# design.net
KiCad netlist of a schematic drawn in Altium Designer
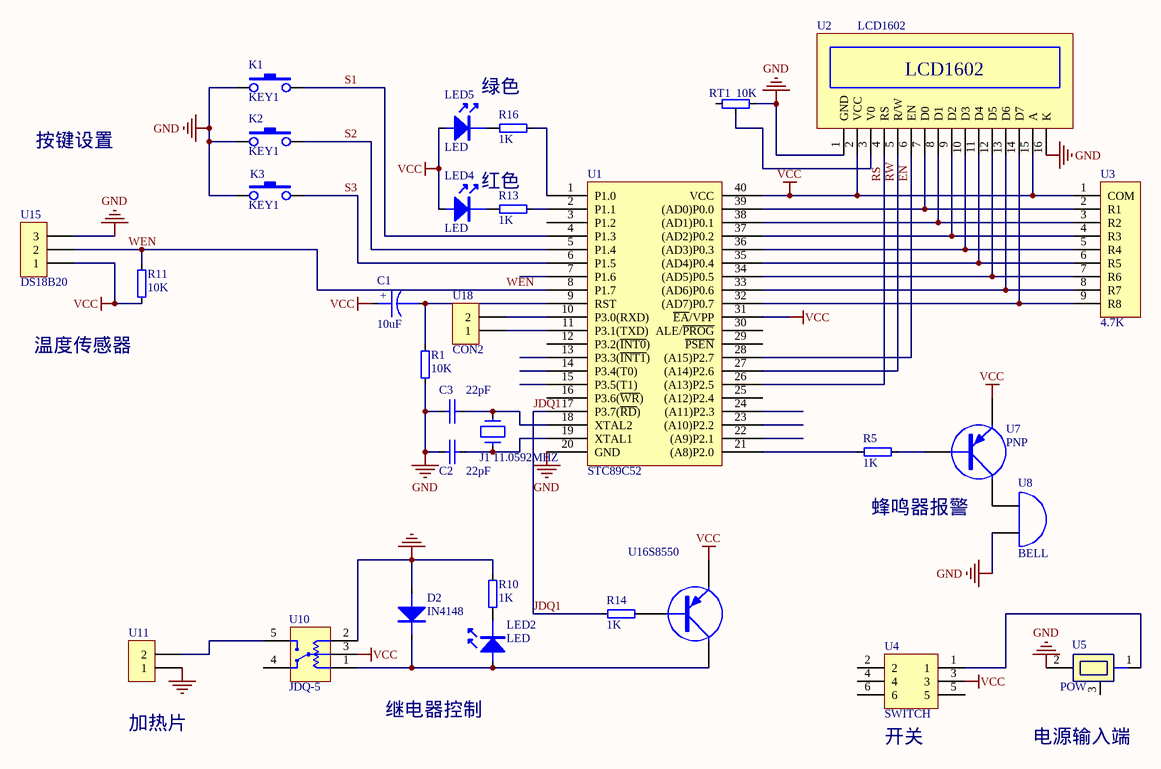
[diagram p0: 原理图.SchDoc]

(export (version "E")
  (design (tool "Eeschema 10.0.6"))
  (components
    (comp (ref "C1") (value "10uF") (footprint "C10") (libsource (lib "51SCH") (part "10uF")))
    (comp (ref "C2") (value "22pF") (footprint "CAP") (libsource (lib "51SCH") (part "0.1uF")))
    (comp (ref "C3") (value "22pF") (footprint "CAP") (libsource (lib "51SCH") (part "0.1uF")))
    (comp (ref "D2") (value "IN4148") (footprint "IN4148") (libsource (lib "*") (part "DIODE")))
    (comp (ref "J1") (value "11.0592MHZ") (footprint "CRYSTAL") (libsource (lib "51SCH") (part "CRYSTAL")))
    (comp (ref "K1") (value "KEY1") (footprint "KEY1") (libsource (lib "51SCH") (part "KEY1")))
    (comp (ref "K2") (value "KEY1") (footprint "KEY1") (libsource (lib "51SCH") (part "KEY1")))
    (comp (ref "K3") (value "KEY1") (footprint "KEY1") (libsource (lib "51SCH") (part "KEY1")))
    (comp (ref "LED2") (value "LED") (footprint "LED") (libsource (lib "*") (part "LED")))
    (comp (ref "LED4") (value "LED") (footprint "LED") (libsource (lib "*") (part "LED")))
    (comp (ref "LED5") (value "LED") (footprint "LED") (libsource (lib "*") (part "LED")))
    (comp (ref "R1") (value "10K") (footprint "R-DIP") (libsource (lib "51SCH") (part "10K")))
    (comp (ref "R5") (value "1K") (footprint "R-DIP") (libsource (lib "51SCH") (part "1K")))
    (comp (ref "R10") (value "1K") (footprint "R-DIP") (libsource (lib "*") (part "1K")))
    (comp (ref "R11") (value "10K") (footprint "R-DIP") (libsource (lib "51SCH") (part "10K")))
    (comp (ref "R13") (value "1K") (footprint "R-DIP") (libsource (lib "*") (part "1K")))
    (comp (ref "R14") (value "1K") (footprint "R-DIP") (libsource (lib "*") (part "1K")))
    (comp (ref "R16") (value "1K") (footprint "R-DIP") (libsource (lib "*") (part "1K")))
    (comp (ref "RT1") (value "10K") (footprint "RT1") (libsource (lib "51SCH") (part "RT")))
    (comp (ref "U1") (value "STC89C52") (footprint "STC") (libsource (lib "51SCH") (part "STC51")))
    (comp (ref "U2") (value "LCD1602") (footprint "LCD1602") (libsource (lib "51SCH") (part "LCD1602")))
    (comp (ref "U3") (value "4.7K") (footprint "SIP9") (libsource (lib "51SCH") (part "PAIZU")))
    (comp (ref "U4") (value "SWITCH") (footprint "KG1") (libsource (lib "51SCH") (part "SWITCH")))
    (comp (ref "U5") (value "POW") (footprint "DCM") (libsource (lib "51SCH") (part "POW")))
    (comp (ref "U7") (value "PNP") (footprint "PNP") (libsource (lib "51SCH") (part "PNP")))
    (comp (ref "U8") (value "BELL") (footprint "BEEP") (libsource (lib "51SCH") (part "BELL")))
    (comp (ref "U10") (value "JDQ-5") (footprint "JDQ-5") (libsource (lib "*") (part "JDQ-5")))
    (comp (ref "U11") (value "~") (footprint "SIP2") (libsource (lib "*") (part "CON2")))
    (comp (ref "U15") (value "DS18B20") (footprint "SIP3") (libsource (lib "51SCH") (part "CON3")))
    (comp (ref "U16S8550") (value "~") (footprint "PNP") (libsource (lib "*") (part "PNP")))
    (comp (ref "U18") (value "CON2") (footprint "SIP2") (libsource (lib "51SCH") (part "CON2")))
  )
  (nets
    (net (code "1") (name "/EN") (class "Default")
      (node (ref "U1") (pin "28") (pinfunction "(A15)P2.7_28") (pintype "passive"))
      (node (ref "U2") (pin "6") (pinfunction "EN_6") (pintype "passive"))
    )
    (net (code "2") (name "/JDQ1") (class "Default")
      (node (ref "R14") (pin "1") (pinfunction "1_1") (pintype "passive"))
      (node (ref "U1") (pin "17") (pinfunction "P3.7(~{RD})_17") (pintype "passive"))
    )
    (net (code "3") (name "/RS") (class "Default")
      (node (ref "U1") (pin "26") (pinfunction "(A13)P2.5_26") (pintype "passive"))
      (node (ref "U2") (pin "4") (pinfunction "RS_4") (pintype "passive"))
    )
    (net (code "4") (name "/RW") (class "Default")
      (node (ref "U1") (pin "27") (pinfunction "(A14)P2.6_27") (pintype "passive"))
      (node (ref "U2") (pin "5") (pinfunction "R/W_5") (pintype "passive"))
    )
    (net (code "5") (name "/S1") (class "Default")
      (node (ref "K1") (pin "2") (pinfunction "10_2") (pintype "passive"))
      (node (ref "U1") (pin "4") (pinfunction "P1.3_4") (pintype "passive"))
    )
    (net (code "6") (name "/S2") (class "Default")
      (node (ref "K2") (pin "2") (pinfunction "10_2") (pintype "passive"))
      (node (ref "U1") (pin "5") (pinfunction "P1.4_5") (pintype "passive"))
    )
    (net (code "7") (name "/S3") (class "Default")
      (node (ref "K3") (pin "2") (pinfunction "10_2") (pintype "passive"))
      (node (ref "U1") (pin "6") (pinfunction "P1.5_6") (pintype "passive"))
    )
    (net (code "8") (name "/WEN") (class "Default")
      (node (ref "R11") (pin "2") (pinfunction "2_2") (pintype "passive"))
      (node (ref "U1") (pin "8") (pinfunction "P1.7_8") (pintype "passive"))
      (node (ref "U15") (pin "2") (pinfunction "2_2") (pintype "passive"))
    )
    (net (code "9") (name "GND") (class "Default")
      (node (ref "C2") (pin "1") (pinfunction "1_1") (pintype "passive"))
      (node (ref "C3") (pin "1") (pinfunction "1_1") (pintype "passive"))
      (node (ref "D2") (pin "1") (pinfunction "A_1") (pintype "passive"))
      (node (ref "K1") (pin "1") (pinfunction "1_1") (pintype "passive"))
      (node (ref "K2") (pin "1") (pinfunction "1_1") (pintype "passive"))
      (node (ref "K3") (pin "1") (pinfunction "1_1") (pintype "passive"))
      (node (ref "R1") (pin "2") (pinfunction "2_2") (pintype "passive"))
      (node (ref "R10") (pin "1") (pinfunction "1_1") (pintype "passive"))
      (node (ref "RT1") (pin "3") (pintype "passive"))
      (node (ref "U1") (pin "20") (pinfunction "GND_20") (pintype "passive"))
      (node (ref "U10") (pin "2") (pintype "passive"))
      (node (ref "U11") (pin "1") (pinfunction "1_1") (pintype "passive"))
      (node (ref "U15") (pin "3") (pinfunction "3_3") (pintype "passive"))
      (node (ref "U2") (pin "1") (pinfunction "GND_1") (pintype "passive"))
      (node (ref "U2") (pin "16") (pinfunction "K_16") (pintype "passive"))
      (node (ref "U5") (pin "2") (pintype "passive"))
      (node (ref "U8") (pin "2") (pinfunction "B_2") (pintype "passive"))
    )
    (net (code "10") (name "Net-(D2-K)") (class "Default")
      (node (ref "D2") (pin "2") (pinfunction "K_2") (pintype "passive"))
      (node (ref "LED2") (pin "1") (pinfunction "1_1") (pintype "passive"))
      (node (ref "U10") (pin "1") (pintype "passive"))
      (node (ref "U16S8550") (pin "3") (pinfunction "C_3") (pintype "passive"))
    )
    (net (code "11") (name "Net-(LED2-Pad2)") (class "Default")
      (node (ref "LED2") (pin "2") (pinfunction "2_2") (pintype "passive"))
      (node (ref "R10") (pin "2") (pinfunction "2_2") (pintype "passive"))
    )
    (net (code "12") (name "Net-(LED4-Pad2)") (class "Default")
      (node (ref "LED4") (pin "2") (pinfunction "2_2") (pintype "passive"))
      (node (ref "R13") (pin "2") (pinfunction "2_2") (pintype "passive"))
    )
    (net (code "13") (name "Net-(LED5-Pad2)") (class "Default")
      (node (ref "LED5") (pin "2") (pinfunction "2_2") (pintype "passive"))
      (node (ref "R16") (pin "2") (pinfunction "2_2") (pintype "passive"))
    )
    (net (code "14") (name "Net-(U1-(A8)P2.0)") (class "Default")
      (node (ref "R5") (pin "1") (pinfunction "1_1") (pintype "passive"))
      (node (ref "U1") (pin "21") (pinfunction "(A8)P2.0_21") (pintype "passive"))
    )
    (net (code "15") (name "Net-(U1-(AD0)P0.0)") (class "Default")
      (node (ref "U1") (pin "39") (pinfunction "(AD0)P0.0_39") (pintype "passive"))
      (node (ref "U2") (pin "7") (pinfunction "D0_7") (pintype "passive"))
      (node (ref "U3") (pin "2") (pinfunction "R1_2") (pintype "passive"))
    )
    (net (code "16") (name "Net-(U1-(AD1)P0.1)") (class "Default")
      (node (ref "U1") (pin "38") (pinfunction "(AD1)P0.1_38") (pintype "passive"))
      (node (ref "U2") (pin "8") (pinfunction "D1_8") (pintype "passive"))
      (node (ref "U3") (pin "3") (pinfunction "R2_3") (pintype "passive"))
    )
    (net (code "17") (name "Net-(U1-(AD2)P0.2)") (class "Default")
      (node (ref "U1") (pin "37") (pinfunction "(AD2)P0.2_37") (pintype "passive"))
      (node (ref "U2") (pin "9") (pinfunction "D2_9") (pintype "passive"))
      (node (ref "U3") (pin "4") (pinfunction "R3_4") (pintype "passive"))
    )
    (net (code "18") (name "Net-(U1-(AD3)P0.3)") (class "Default")
      (node (ref "U1") (pin "36") (pinfunction "(AD3)P0.3_36") (pintype "passive"))
      (node (ref "U2") (pin "10") (pinfunction "D3_10") (pintype "passive"))
      (node (ref "U3") (pin "5") (pinfunction "R4_5") (pintype "passive"))
    )
    (net (code "19") (name "Net-(U1-(AD4)P0.4)") (class "Default")
      (node (ref "U1") (pin "35") (pinfunction "(AD4)P0.4_35") (pintype "passive"))
      (node (ref "U2") (pin "11") (pinfunction "D4_11") (pintype "passive"))
      (node (ref "U3") (pin "6") (pinfunction "R5_6") (pintype "passive"))
    )
    (net (code "20") (name "Net-(U1-(AD5)P0.5)") (class "Default")
      (node (ref "U1") (pin "34") (pinfunction "(AD5)P0.5_34") (pintype "passive"))
      (node (ref "U2") (pin "12") (pinfunction "D5_12") (pintype "passive"))
      (node (ref "U3") (pin "7") (pinfunction "R6_7") (pintype "passive"))
    )
    (net (code "21") (name "Net-(U1-(AD6)P0.6)") (class "Default")
      (node (ref "U1") (pin "33") (pinfunction "(AD6)P0.6_33") (pintype "passive"))
      (node (ref "U2") (pin "13") (pinfunction "D6_13") (pintype "passive"))
      (node (ref "U3") (pin "8") (pinfunction "R7_8") (pintype "passive"))
    )
    (net (code "22") (name "Net-(U1-(AD7)P0.7)") (class "Default")
      (node (ref "U1") (pin "32") (pinfunction "(AD7)P0.7_32") (pintype "passive"))
      (node (ref "U2") (pin "14") (pinfunction "D7_14") (pintype "passive"))
      (node (ref "U3") (pin "9") (pinfunction "R8_9") (pintype "passive"))
    )
    (net (code "23") (name "Net-(U1-P1.0)") (class "Default")
      (node (ref "R16") (pin "1") (pinfunction "1_1") (pintype "passive"))
      (node (ref "U1") (pin "1") (pinfunction "P1.0_1") (pintype "passive"))
    )
    (net (code "24") (name "Net-(U1-P1.1)") (class "Default")
      (node (ref "R13") (pin "1") (pinfunction "1_1") (pintype "passive"))
      (node (ref "U1") (pin "2") (pinfunction "P1.1_2") (pintype "passive"))
    )
    (net (code "25") (name "Net-(U1-P3.0(RXD))") (class "Default")
      (node (ref "U1") (pin "10") (pinfunction "P3.0(RXD)_10") (pintype "passive"))
      (node (ref "U18") (pin "2") (pinfunction "2_2") (pintype "passive"))
    )
    (net (code "26") (name "Net-(U1-P3.1(TXD))") (class "Default")
      (node (ref "U1") (pin "11") (pinfunction "P3.1(TXD)_11") (pintype "passive"))
      (node (ref "U18") (pin "1") (pinfunction "1_1") (pintype "passive"))
    )
    (net (code "27") (name "Net-(U1-RST)") (class "Default")
      (node (ref "C1") (pin "2") (pinfunction "2_2") (pintype "passive"))
      (node (ref "R1") (pin "1") (pinfunction "1_1") (pintype "passive"))
      (node (ref "U1") (pin "9") (pinfunction "RST_9") (pintype "passive"))
    )
    (net (code "28") (name "Net-(U1-XTAL1)") (class "Default")
      (node (ref "C3") (pin "2") (pinfunction "2_2") (pintype "passive"))
      (node (ref "J1") (pin "1") (pinfunction "1_1") (pintype "passive"))
      (node (ref "U1") (pin "19") (pinfunction "XTAL1_19") (pintype "passive"))
    )
    (net (code "29") (name "Net-(U1-XTAL2)") (class "Default")
      (node (ref "C2") (pin "2") (pinfunction "2_2") (pintype "passive"))
      (node (ref "J1") (pin "2") (pinfunction "2_2") (pintype "passive"))
      (node (ref "U1") (pin "18") (pinfunction "XTAL2_18") (pintype "passive"))
    )
    (net (code "30") (name "Net-(U2-V0)") (class "Default")
      (node (ref "RT1") (pin "2") (pintype "passive"))
      (node (ref "U2") (pin "3") (pinfunction "V0_3") (pintype "passive"))
    )
    (net (code "31") (name "Net-(U4-Pad1)") (class "Default")
      (node (ref "U4") (pin "1") (pinfunction "1_1") (pintype "passive"))
      (node (ref "U5") (pin "1") (pintype "passive"))
    )
    (net (code "32") (name "Net-(U7-B)") (class "Default")
      (node (ref "R5") (pin "2") (pinfunction "2_2") (pintype "passive"))
      (node (ref "U7") (pin "1") (pinfunction "B_1") (pintype "passive"))
    )
    (net (code "33") (name "Net-(U7-C)") (class "Default")
      (node (ref "U7") (pin "3") (pinfunction "C_3") (pintype "passive"))
      (node (ref "U8") (pin "1") (pinfunction "A_1") (pintype "passive"))
    )
    (net (code "34") (name "Net-(U10-IN-Pad5)") (class "Default")
      (node (ref "U10") (pin "5") (pinfunction "IN_5") (pintype "passive"))
      (node (ref "U11") (pin "2") (pinfunction "2_2") (pintype "passive"))
    )
    (net (code "35") (name "Net-(U16S8550-B)") (class "Default")
      (node (ref "R14") (pin "2") (pinfunction "2_2") (pintype "passive"))
      (node (ref "U16S8550") (pin "1") (pinfunction "B_1") (pintype "passive"))
    )
    (net (code "36") (name "VCC") (class "Default")
      (node (ref "C1") (pin "1") (pinfunction "1_1") (pintype "passive"))
      (node (ref "LED4") (pin "1") (pinfunction "1_1") (pintype "passive"))
      (node (ref "LED5") (pin "1") (pinfunction "1_1") (pintype "passive"))
      (node (ref "R11") (pin "1") (pinfunction "1_1") (pintype "passive"))
      (node (ref "U1") (pin "31") (pinfunction "~{EA}/VPP_31") (pintype "passive"))
      (node (ref "U1") (pin "40") (pinfunction "VCC_40") (pintype "passive"))
      (node (ref "U10") (pin "3") (pinfunction "IN_3") (pintype "passive"))
      (node (ref "U15") (pin "1") (pinfunction "1_1") (pintype "passive"))
      (node (ref "U16S8550") (pin "2") (pinfunction "E_2") (pintype "passive"))
      (node (ref "U2") (pin "15") (pinfunction "A_15") (pintype "passive"))
      (node (ref "U2") (pin "2") (pinfunction "VCC_2") (pintype "passive"))
      (node (ref "U3") (pin "1") (pinfunction "COM_1") (pintype "passive"))
      (node (ref "U4") (pin "3") (pinfunction "3_3") (pintype "passive"))
      (node (ref "U7") (pin "2") (pinfunction "E_2") (pintype "passive"))
    )
    (net (code "37") (name "unconnected-(RT1-Pad1)") (class "Default")
      (node (ref "RT1") (pin "1") (pintype "passive"))
    )
    (net (code "38") (name "unconnected-(U1-(A9)P2.1-Pad22)") (class "Default")
      (node (ref "U1") (pin "22") (pinfunction "(A9)P2.1_22") (pintype "passive"))
    )
    (net (code "39") (name "unconnected-(U1-(A10)P2.2-Pad23)") (class "Default")
      (node (ref "U1") (pin "23") (pinfunction "(A10)P2.2_23") (pintype "passive"))
    )
    (net (code "40") (name "unconnected-(U1-(A11)P2.3-Pad24)") (class "Default")
      (node (ref "U1") (pin "24") (pinfunction "(A11)P2.3_24") (pintype "passive"))
    )
    (net (code "41") (name "unconnected-(U1-(A12)P2.4-Pad25)") (class "Default")
      (node (ref "U1") (pin "25") (pinfunction "(A12)P2.4_25") (pintype "passive"))
    )
    (net (code "42") (name "unconnected-(U1-ALE{slash}~{PROG}-Pad30)") (class "Default")
      (node (ref "U1") (pin "30") (pinfunction "ALE/~{PROG}_30") (pintype "passive"))
    )
    (net (code "43") (name "unconnected-(U1-P1.2-Pad3)") (class "Default")
      (node (ref "U1") (pin "3") (pinfunction "P1.2_3") (pintype "passive"))
    )
    (net (code "44") (name "unconnected-(U1-P1.6-Pad7)") (class "Default")
      (node (ref "U1") (pin "7") (pinfunction "P1.6_7") (pintype "passive"))
    )
    (net (code "45") (name "unconnected-(U1-P3.2(~{INT0})-Pad12)") (class "Default")
      (node (ref "U1") (pin "12") (pinfunction "P3.2(~{INT0})_12") (pintype "passive"))
    )
    (net (code "46") (name "unconnected-(U1-P3.3(~{INT1})-Pad13)") (class "Default")
      (node (ref "U1") (pin "13") (pinfunction "P3.3(~{INT1})_13") (pintype "passive"))
    )
    (net (code "47") (name "unconnected-(U1-P3.4(T0)-Pad14)") (class "Default")
      (node (ref "U1") (pin "14") (pinfunction "P3.4(T0)_14") (pintype "passive"))
    )
    (net (code "48") (name "unconnected-(U1-P3.5(T1)-Pad15)") (class "Default")
      (node (ref "U1") (pin "15") (pinfunction "P3.5(T1)_15") (pintype "passive"))
    )
    (net (code "49") (name "unconnected-(U1-P3.6(~{WR})-Pad16)") (class "Default")
      (node (ref "U1") (pin "16") (pinfunction "P3.6(~{WR})_16") (pintype "passive"))
    )
    (net (code "50") (name "unconnected-(U1-~{PSEN}-Pad29)") (class "Default")
      (node (ref "U1") (pin "29") (pinfunction "~{PSEN}_29") (pintype "passive"))
    )
    (net (code "51") (name "unconnected-(U4-Pad2)") (class "Default")
      (node (ref "U4") (pin "2") (pinfunction "2_2") (pintype "passive"))
    )
    (net (code "52") (name "unconnected-(U4-Pad4)") (class "Default")
      (node (ref "U4") (pin "4") (pinfunction "4_4") (pintype "passive"))
    )
    (net (code "53") (name "unconnected-(U4-Pad5)") (class "Default")
      (node (ref "U4") (pin "5") (pinfunction "5_5") (pintype "passive"))
    )
    (net (code "54") (name "unconnected-(U4-Pad6)") (class "Default")
      (node (ref "U4") (pin "6") (pinfunction "6_6") (pintype "passive"))
    )
    (net (code "55") (name "unconnected-(U5-Pad3)") (class "Default")
      (node (ref "U5") (pin "3") (pintype "passive"))
    )
    (net (code "56") (name "unconnected-(U10-IN-Pad4)") (class "Default")
      (node (ref "U10") (pin "4") (pinfunction "IN_4") (pintype "passive"))
    )
  )
)
